# MagneticFieldDetection.net
KiCad netlist of a schematic drawn in Altium Designer
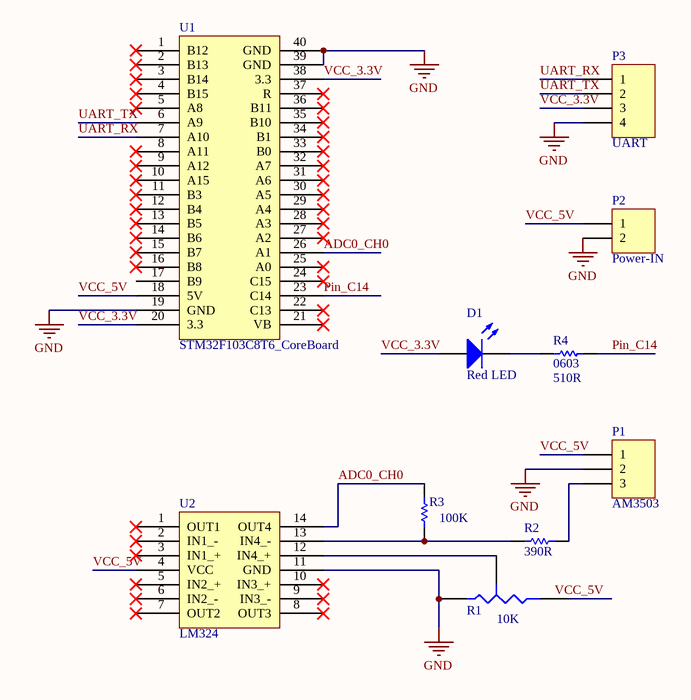
[diagram p0: MagneticFieldDetection.SchDoc]

(export (version "E")
  (design (tool "Eeschema 10.0.6"))
  (components
    (comp (ref "D1")
      (value "Red LED")
      (footprint "LED-0")
      (description "Typical INFRARED GaAs LED")
      (fields (field (name "PUBLISHER") "Altium Limited"))
      (libsource (lib "Miscellaneous Devices") (part "LED0"))
    )
    (comp (ref "P1")
      (value "AM3503")
      (footprint "HDR1X3")
      (description "Header, 3-Pin")
      (fields (field (name "PUBLISHER") "Altium Limited"))
      (libsource (lib "Miscellaneous Connectors") (part "Header 3"))
    )
    (comp (ref "P2")
      (value "Power-IN")
      (footprint "HDR1X2")
      (description "Header, 2-Pin")
      (fields (field (name "PUBLISHER") "Altium Limited"))
      (libsource (lib "Miscellaneous Connectors") (part "Header 2"))
    )
    (comp (ref "P3")
      (value "UART")
      (footprint "HDR1X4H")
      (description "Header, 4-Pin, Right Angle")
      (fields (field (name "PUBLISHER") "Altium Limited"))
      (libsource (lib "Miscellaneous Connectors") (part "Header 4H"))
    )
    (comp (ref "R1")
      (value "10K")
      (footprint "VR3")
      (description "Tapped Resistor")
      (fields (field (name "Comment") "Res Tap") (field (name "PUBLISHER") "Altium Limited"))
      (libsource (lib "Miscellaneous Devices") (part "Res Tap"))
    )
    (comp (ref "R2")
      (value "390R")
      (footprint "AXIAL-0.5")
      (description "Semiconductor Resistor")
      (fields (field (name "Comment") "Res Semi") (field (name "PUBLISHER") "Altium Limited"))
      (libsource (lib "Miscellaneous Devices") (part "Res Semi"))
    )
    (comp (ref "R3")
      (value "100K")
      (footprint "AXIAL-0.5")
      (description "Semiconductor Resistor")
      (fields (field (name "Comment") "Res Semi") (field (name "PUBLISHER") "Altium Limited"))
      (libsource (lib "Miscellaneous Devices") (part "Res Semi"))
    )
    (comp (ref "R4")
      (value "0603")
      (footprint "AXIAL-0.3")
      (description "Resistor")
      (fields (field (name "ALTIUM_VALUE") "510R") (field (name "PUBLISHER") "Altium Limited"))
      (libsource (lib "Miscellaneous Devices") (part "Res1"))
    )
    (comp (ref "U1")
      (value "STM32F103C8T6_CoreBoard")
      (libsource (lib "GavinPCBLib") (part "STM32F103C8T6_CoreBoard"))
    )
    (comp (ref "U2") (value "LM324") (footprint "LM324") (libsource (lib "常用芯片类") (part "LM324")))
  )
  (nets
    (net (code "1") (name "/ADC0_CH0") (class "Default")
      (node (ref "R3") (pin "2") (pinfunction "2_2") (pintype "passive"))
      (node (ref "U1") (pin "26") (pinfunction "A1_26") (pintype "passive"))
      (node (ref "U2") (pin "14") (pinfunction "OUT4_14") (pintype "passive"))
    )
    (net (code "2") (name "/Pin_C14") (class "Default")
      (node (ref "R4") (pin "2") (pinfunction "2_2") (pintype "passive"))
      (node (ref "U1") (pin "23") (pinfunction "C14_23") (pintype "passive"))
    )
    (net (code "3") (name "/UART_RX") (class "Default")
      (node (ref "P3") (pin "1") (pinfunction "1_1") (pintype "passive"))
      (node (ref "U1") (pin "7") (pinfunction "A10_7") (pintype "passive"))
    )
    (net (code "4") (name "/UART_TX") (class "Default")
      (node (ref "P3") (pin "2") (pinfunction "2_2") (pintype "passive"))
      (node (ref "U1") (pin "6") (pinfunction "A9_6") (pintype "passive"))
    )
    (net (code "5") (name "/VCC_3.3V") (class "Default")
      (node (ref "D1") (pin "1") (pinfunction "A_1") (pintype "passive"))
      (node (ref "P3") (pin "3") (pinfunction "3_3") (pintype "passive"))
      (node (ref "U1") (pin "20") (pinfunction "3.3_20") (pintype "passive"))
      (node (ref "U1") (pin "38") (pinfunction "3.3_38") (pintype "passive"))
    )
    (net (code "6") (name "/VCC_5V") (class "Default")
      (node (ref "P1") (pin "1") (pinfunction "1_1") (pintype "passive"))
      (node (ref "P2") (pin "1") (pinfunction "1_1") (pintype "passive"))
      (node (ref "U1") (pin "18") (pinfunction "5V_18") (pintype "passive"))
      (node (ref "U2") (pin "4") (pinfunction "VCC_4") (pintype "passive"))
    )
    (net (code "7") (name "GND") (class "Default")
      (node (ref "P1") (pin "2") (pinfunction "2_2") (pintype "passive"))
      (node (ref "P2") (pin "2") (pinfunction "2_2") (pintype "passive"))
      (node (ref "P3") (pin "4") (pinfunction "4_4") (pintype "passive"))
      (node (ref "R1") (pin "1") (pinfunction "A_1") (pintype "passive"))
      (node (ref "U1") (pin "19") (pinfunction "GND_19") (pintype "passive"))
      (node (ref "U1") (pin "39") (pinfunction "GND_39") (pintype "passive"))
      (node (ref "U1") (pin "40") (pinfunction "GND_40") (pintype "passive"))
      (node (ref "U2") (pin "11") (pinfunction "GND_11") (pintype "passive"))
    )
    (net (code "8") (name "Net-(D1-K)") (class "Default")
      (node (ref "D1") (pin "2") (pinfunction "K_2") (pintype "passive"))
      (node (ref "R4") (pin "1") (pinfunction "1_1") (pintype "passive"))
    )
    (net (code "9") (name "Net-(P1-Pad3)") (class "Default")
      (node (ref "P1") (pin "3") (pinfunction "3_3") (pintype "passive"))
      (node (ref "R2") (pin "1") (pinfunction "1_1") (pintype "passive"))
    )
    (net (code "10") (name "Net-(R1-TAP)") (class "Default")
      (node (ref "R1") (pin "3") (pinfunction "TAP_3") (pintype "passive"))
      (node (ref "U2") (pin "12") (pinfunction "IN4_+_12") (pintype "passive"))
    )
    (net (code "11") (name "Net-(U2-IN4_-)") (class "Default")
      (node (ref "R2") (pin "2") (pinfunction "2_2") (pintype "passive"))
      (node (ref "R3") (pin "1") (pinfunction "1_1") (pintype "passive"))
      (node (ref "U2") (pin "13") (pinfunction "IN4_-_13") (pintype "passive"))
    )
    (net (code "12") (name "unconnected-(R1-B-Pad2)") (class "Default")
      (node (ref "R1") (pin "2") (pinfunction "B_2") (pintype "passive"))
    )
    (net (code "13") (name "unconnected-(U1-A0-Pad25)") (class "Default")
      (node (ref "U1") (pin "25") (pinfunction "A0_25") (pintype "passive+no_connect"))
    )
    (net (code "14") (name "unconnected-(U1-A2-Pad27)") (class "Default")
      (node (ref "U1") (pin "27") (pinfunction "A2_27") (pintype "passive+no_connect"))
    )
    (net (code "15") (name "unconnected-(U1-A3-Pad28)") (class "Default")
      (node (ref "U1") (pin "28") (pinfunction "A3_28") (pintype "passive+no_connect"))
    )
    (net (code "16") (name "unconnected-(U1-A4-Pad29)") (class "Default")
      (node (ref "U1") (pin "29") (pinfunction "A4_29") (pintype "passive+no_connect"))
    )
    (net (code "17") (name "unconnected-(U1-A5-Pad30)") (class "Default")
      (node (ref "U1") (pin "30") (pinfunction "A5_30") (pintype "passive+no_connect"))
    )
    (net (code "18") (name "unconnected-(U1-A6-Pad31)") (class "Default")
      (node (ref "U1") (pin "31") (pinfunction "A6_31") (pintype "passive+no_connect"))
    )
    (net (code "19") (name "unconnected-(U1-A7-Pad32)") (class "Default")
      (node (ref "U1") (pin "32") (pinfunction "A7_32") (pintype "passive+no_connect"))
    )
    (net (code "20") (name "unconnected-(U1-A8-Pad5)") (class "Default")
      (node (ref "U1") (pin "5") (pinfunction "A8_5") (pintype "passive+no_connect"))
    )
    (net (code "21") (name "unconnected-(U1-A11-Pad8)") (class "Default")
      (node (ref "U1") (pin "8") (pinfunction "A11_8") (pintype "passive+no_connect"))
    )
    (net (code "22") (name "unconnected-(U1-A12-Pad9)") (class "Default")
      (node (ref "U1") (pin "9") (pinfunction "A12_9") (pintype "passive+no_connect"))
    )
    (net (code "23") (name "unconnected-(U1-A15-Pad10)") (class "Default")
      (node (ref "U1") (pin "10") (pinfunction "A15_10") (pintype "passive+no_connect"))
    )
    (net (code "24") (name "unconnected-(U1-B0-Pad33)") (class "Default")
      (node (ref "U1") (pin "33") (pinfunction "B0_33") (pintype "passive+no_connect"))
    )
    (net (code "25") (name "unconnected-(U1-B1-Pad34)") (class "Default")
      (node (ref "U1") (pin "34") (pinfunction "B1_34") (pintype "passive+no_connect"))
    )
    (net (code "26") (name "unconnected-(U1-B3-Pad11)") (class "Default")
      (node (ref "U1") (pin "11") (pinfunction "B3_11") (pintype "passive+no_connect"))
    )
    (net (code "27") (name "unconnected-(U1-B4-Pad12)") (class "Default")
      (node (ref "U1") (pin "12") (pinfunction "B4_12") (pintype "passive+no_connect"))
    )
    (net (code "28") (name "unconnected-(U1-B5-Pad13)") (class "Default")
      (node (ref "U1") (pin "13") (pinfunction "B5_13") (pintype "passive+no_connect"))
    )
    (net (code "29") (name "unconnected-(U1-B6-Pad14)") (class "Default")
      (node (ref "U1") (pin "14") (pinfunction "B6_14") (pintype "passive+no_connect"))
    )
    (net (code "30") (name "unconnected-(U1-B7-Pad15)") (class "Default")
      (node (ref "U1") (pin "15") (pinfunction "B7_15") (pintype "passive+no_connect"))
    )
    (net (code "31") (name "unconnected-(U1-B8-Pad16)") (class "Default")
      (node (ref "U1") (pin "16") (pinfunction "B8_16") (pintype "passive+no_connect"))
    )
    (net (code "32") (name "unconnected-(U1-B9-Pad17)") (class "Default")
      (node (ref "U1") (pin "17") (pinfunction "B9_17") (pintype "passive"))
    )
    (net (code "33") (name "unconnected-(U1-B10-Pad35)") (class "Default")
      (node (ref "U1") (pin "35") (pinfunction "B10_35") (pintype "passive+no_connect"))
    )
    (net (code "34") (name "unconnected-(U1-B11-Pad36)") (class "Default")
      (node (ref "U1") (pin "36") (pinfunction "B11_36") (pintype "passive+no_connect"))
    )
    (net (code "35") (name "unconnected-(U1-B12-Pad1)") (class "Default")
      (node (ref "U1") (pin "1") (pinfunction "B12_1") (pintype "passive+no_connect"))
    )
    (net (code "36") (name "unconnected-(U1-B13-Pad2)") (class "Default")
      (node (ref "U1") (pin "2") (pinfunction "B13_2") (pintype "passive+no_connect"))
    )
    (net (code "37") (name "unconnected-(U1-B14-Pad3)") (class "Default")
      (node (ref "U1") (pin "3") (pinfunction "B14_3") (pintype "passive+no_connect"))
    )
    (net (code "38") (name "unconnected-(U1-B15-Pad4)") (class "Default")
      (node (ref "U1") (pin "4") (pinfunction "B15_4") (pintype "passive+no_connect"))
    )
    (net (code "39") (name "unconnected-(U1-C13-Pad22)") (class "Default")
      (node (ref "U1") (pin "22") (pinfunction "C13_22") (pintype "passive+no_connect"))
    )
    (net (code "40") (name "unconnected-(U1-C15-Pad24)") (class "Default")
      (node (ref "U1") (pin "24") (pinfunction "C15_24") (pintype "passive+no_connect"))
    )
    (net (code "41") (name "unconnected-(U1-R-Pad37)") (class "Default")
      (node (ref "U1") (pin "37") (pinfunction "R_37") (pintype "passive+no_connect"))
    )
    (net (code "42") (name "unconnected-(U1-VB-Pad21)") (class "Default")
      (node (ref "U1") (pin "21") (pinfunction "VB_21") (pintype "passive+no_connect"))
    )
    (net (code "43") (name "unconnected-(U2-IN1_+-Pad3)") (class "Default")
      (node (ref "U2") (pin "3") (pinfunction "IN1_+_3") (pintype "passive+no_connect"))
    )
    (net (code "44") (name "unconnected-(U2-IN1_--Pad2)") (class "Default")
      (node (ref "U2") (pin "2") (pinfunction "IN1_-_2") (pintype "passive+no_connect"))
    )
    (net (code "45") (name "unconnected-(U2-IN2_+-Pad5)") (class "Default")
      (node (ref "U2") (pin "5") (pinfunction "IN2_+_5") (pintype "passive+no_connect"))
    )
    (net (code "46") (name "unconnected-(U2-IN2_--Pad6)") (class "Default")
      (node (ref "U2") (pin "6") (pinfunction "IN2_-_6") (pintype "passive+no_connect"))
    )
    (net (code "47") (name "unconnected-(U2-IN3_+-Pad10)") (class "Default")
      (node (ref "U2") (pin "10") (pinfunction "IN3_+_10") (pintype "passive+no_connect"))
    )
    (net (code "48") (name "unconnected-(U2-IN3_--Pad9)") (class "Default")
      (node (ref "U2") (pin "9") (pinfunction "IN3_-_9") (pintype "passive+no_connect"))
    )
    (net (code "49") (name "unconnected-(U2-OUT1-Pad1)") (class "Default")
      (node (ref "U2") (pin "1") (pinfunction "OUT1_1") (pintype "passive+no_connect"))
    )
    (net (code "50") (name "unconnected-(U2-OUT2-Pad7)") (class "Default")
      (node (ref "U2") (pin "7") (pinfunction "OUT2_7") (pintype "passive+no_connect"))
    )
    (net (code "51") (name "unconnected-(U2-OUT3-Pad8)") (class "Default")
      (node (ref "U2") (pin "8") (pinfunction "OUT3_8") (pintype "passive+no_connect"))
    )
  )
)
